# filter.net
KiCad netlist of a schematic drawn in EAGLE
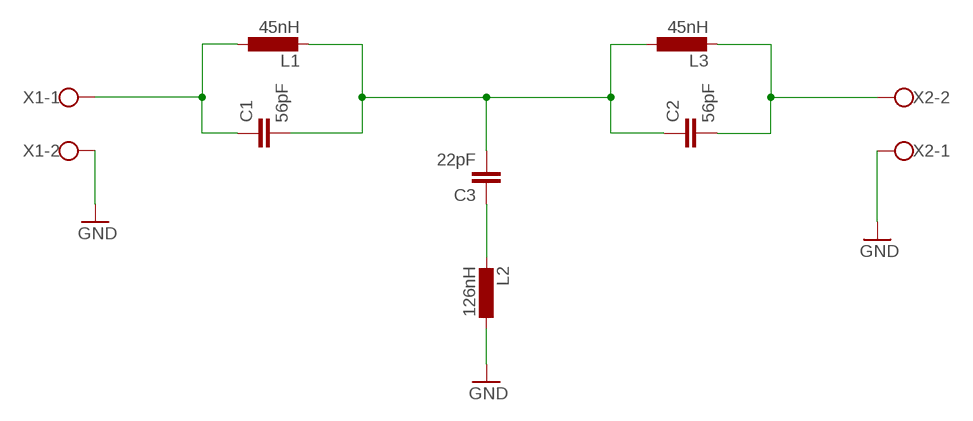
[diagram p0: schematic, sheet 1]

(export (version "E")
  (design (tool "Eeschema 10.0.6"))
  (components
    (comp (ref "C1")
      (value "56pF")
      (footprint "eagle-import:C0805K")
      (libsource (lib "eagle-import") (part "C-EUC0805K"))
    )
    (comp (ref "C2")
      (value "56pF")
      (footprint "eagle-import:C0805K")
      (libsource (lib "eagle-import") (part "C-EUC0805K"))
    )
    (comp (ref "C3")
      (value "22pF")
      (footprint "eagle-import:C0805K")
      (libsource (lib "eagle-import") (part "C-EUC0805K"))
    )
    (comp (ref "L1")
      (value "45nH")
      (footprint "eagle-import:0204_7")
      (libsource (lib "eagle-import") (part "L-EU0204/7"))
    )
    (comp (ref "L2")
      (value "126nH")
      (footprint "eagle-import:0207_10")
      (libsource (lib "eagle-import") (part "L-EU0207/10"))
    )
    (comp (ref "L3")
      (value "45nH")
      (footprint "eagle-import:0204_7")
      (libsource (lib "eagle-import") (part "L-EU0204/7"))
    )
    (comp (ref "X1")
      (value "W237-102")
      (footprint "eagle-import:W237-102")
      (fields (field (name "MPN") "237-102"))
      (libsource (lib "eagle-import") (part "W237-102"))
    )
    (comp (ref "X2")
      (value "W237-102")
      (footprint "eagle-import:W237-102")
      (fields (field (name "MPN") "237-102"))
      (libsource (lib "eagle-import") (part "W237-102"))
    )
  )
  (nets
    (net (code "1") (name "GND") (class "Default")
      (node (ref "L2") (pin "1") (pinfunction "1_1") (pintype "passive"))
      (node (ref "X1") (pin "2") (pinfunction "KL_2") (pintype "passive"))
      (node (ref "X2") (pin "1") (pinfunction "KL_1") (pintype "passive"))
    )
    (net (code "2") (name "Net-(C1-Pad2)") (class "Default")
      (node (ref "C1") (pin "2") (pinfunction "2_2") (pintype "passive"))
      (node (ref "C2") (pin "1") (pinfunction "1_1") (pintype "passive"))
      (node (ref "C3") (pin "2") (pinfunction "2_2") (pintype "passive"))
      (node (ref "L1") (pin "2") (pinfunction "2_2") (pintype "passive"))
      (node (ref "L3") (pin "1") (pinfunction "1_1") (pintype "passive"))
    )
    (net (code "3") (name "Net-(C3-Pad1)") (class "Default")
      (node (ref "C3") (pin "1") (pinfunction "1_1") (pintype "passive"))
      (node (ref "L2") (pin "2") (pinfunction "2_2") (pintype "passive"))
    )
    (net (code "4") (name "Net-(X1A-KL)") (class "Default")
      (node (ref "C1") (pin "1") (pinfunction "1_1") (pintype "passive"))
      (node (ref "L1") (pin "1") (pinfunction "1_1") (pintype "passive"))
      (node (ref "X1") (pin "1") (pinfunction "KL_1") (pintype "passive"))
    )
    (net (code "5") (name "Net-(X2B-KL)") (class "Default")
      (node (ref "C2") (pin "2") (pinfunction "2_2") (pintype "passive"))
      (node (ref "L3") (pin "2") (pinfunction "2_2") (pintype "passive"))
      (node (ref "X2") (pin "2") (pinfunction "KL_2") (pintype "passive"))
    )
  )
)
